# actuator-module.net
KiCad netlist of a schematic drawn in EAGLE
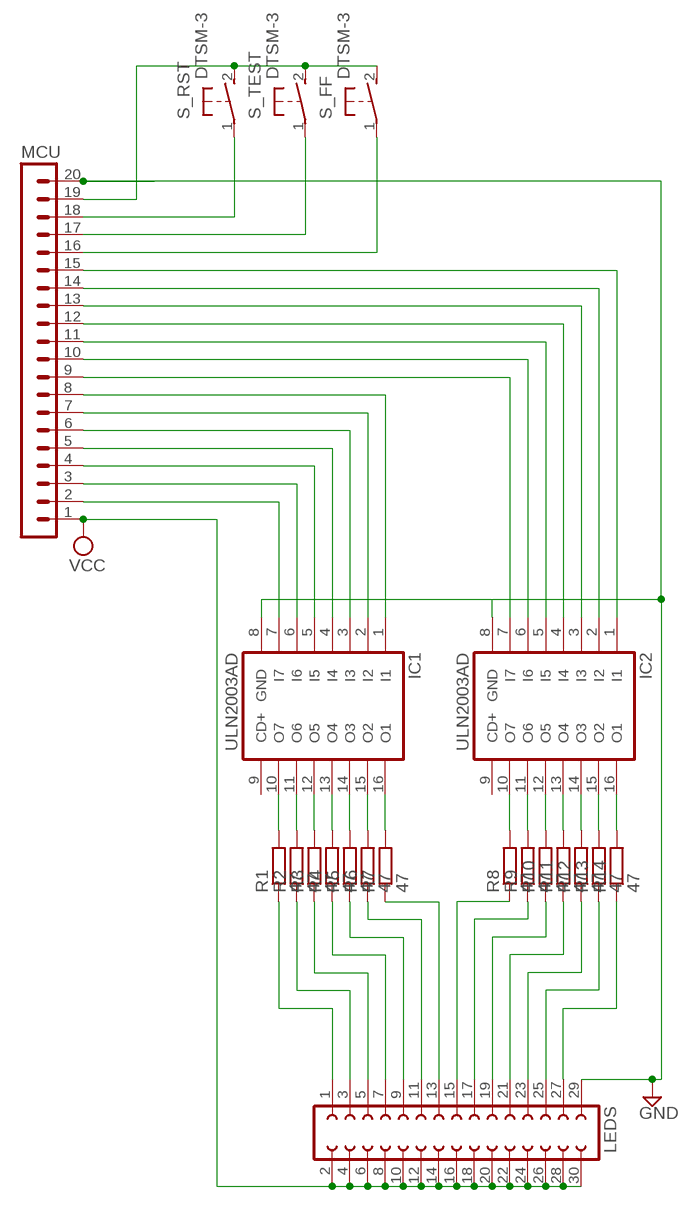
[diagram p0: schematic, sheet 1]

(export (version "E")
  (design (tool "Eeschema 10.0.6"))
  (components
    (comp (ref "IC1")
      (value "ULN2003AD")
      (footprint "eagle-import:SO16")
      (libsource (lib "eagle-import") (part "ULN2003AD"))
    )
    (comp (ref "IC2")
      (value "ULN2003AD")
      (footprint "eagle-import:SO16")
      (libsource (lib "eagle-import") (part "ULN2003AD"))
    )
    (comp (ref "LEDS")
      (value "FE15-2")
      (footprint "eagle-import:FE15-2")
      (libsource (lib "eagle-import") (part "FE15-2"))
    )
    (comp (ref "MCU")
      (value "MA20-1")
      (footprint "eagle-import:MA20-1")
      (libsource (lib "eagle-import") (part "MA20-1"))
    )
    (comp (ref "R1")
      (value "47")
      (footprint "eagle-import:M0805")
      (libsource (lib "eagle-import") (part "R-EU_M0805"))
    )
    (comp (ref "R2")
      (value "47")
      (footprint "eagle-import:M0805")
      (libsource (lib "eagle-import") (part "R-EU_M0805"))
    )
    (comp (ref "R3")
      (value "47")
      (footprint "eagle-import:M0805")
      (libsource (lib "eagle-import") (part "R-EU_M0805"))
    )
    (comp (ref "R4")
      (value "47")
      (footprint "eagle-import:M0805")
      (libsource (lib "eagle-import") (part "R-EU_M0805"))
    )
    (comp (ref "R5")
      (value "47")
      (footprint "eagle-import:M0805")
      (libsource (lib "eagle-import") (part "R-EU_M0805"))
    )
    (comp (ref "R6")
      (value "47")
      (footprint "eagle-import:M0805")
      (libsource (lib "eagle-import") (part "R-EU_M0805"))
    )
    (comp (ref "R7")
      (value "47")
      (footprint "eagle-import:M0805")
      (libsource (lib "eagle-import") (part "R-EU_M0805"))
    )
    (comp (ref "R8")
      (value "47")
      (footprint "eagle-import:M0805")
      (libsource (lib "eagle-import") (part "R-EU_M0805"))
    )
    (comp (ref "R9")
      (value "47")
      (footprint "eagle-import:M0805")
      (libsource (lib "eagle-import") (part "R-EU_M0805"))
    )
    (comp (ref "R10")
      (value "47")
      (footprint "eagle-import:M0805")
      (libsource (lib "eagle-import") (part "R-EU_M0805"))
    )
    (comp (ref "R11")
      (value "47")
      (footprint "eagle-import:M0805")
      (libsource (lib "eagle-import") (part "R-EU_M0805"))
    )
    (comp (ref "R12")
      (value "47")
      (footprint "eagle-import:M0805")
      (libsource (lib "eagle-import") (part "R-EU_M0805"))
    )
    (comp (ref "R13")
      (value "47")
      (footprint "eagle-import:M0805")
      (libsource (lib "eagle-import") (part "R-EU_M0805"))
    )
    (comp (ref "R14")
      (value "47")
      (footprint "eagle-import:M0805")
      (libsource (lib "eagle-import") (part "R-EU_M0805"))
    )
    (comp (ref "S_FF")
      (value "DTSM-3")
      (footprint "eagle-import:DTSM-3")
      (libsource (lib "eagle-import") (part "DTSM-3"))
    )
    (comp (ref "S_RST")
      (value "DTSM-3")
      (footprint "eagle-import:DTSM-3")
      (libsource (lib "eagle-import") (part "DTSM-3"))
    )
    (comp (ref "S_TEST")
      (value "DTSM-3")
      (footprint "eagle-import:DTSM-3")
      (libsource (lib "eagle-import") (part "DTSM-3"))
    )
  )
  (nets
    (net (code "1") (name "GND") (class "Default")
      (node (ref "IC1") (pin "8") (pinfunction "GND_8") (pintype "power_in"))
      (node (ref "IC2") (pin "8") (pinfunction "GND_8") (pintype "power_in"))
      (node (ref "LEDS") (pin "29") (pinfunction "29_29") (pintype "passive"))
      (node (ref "MCU") (pin "20") (pinfunction "20_20") (pintype "passive"))
    )
    (net (code "2") (name "Net-(IC1-I1)") (class "Default")
      (node (ref "IC1") (pin "1") (pinfunction "I1_1") (pintype "input"))
      (node (ref "MCU") (pin "8") (pinfunction "8_8") (pintype "passive"))
    )
    (net (code "3") (name "Net-(IC1-I2)") (class "Default")
      (node (ref "IC1") (pin "2") (pinfunction "I2_2") (pintype "input"))
      (node (ref "MCU") (pin "7") (pinfunction "7_7") (pintype "passive"))
    )
    (net (code "4") (name "Net-(IC1-I3)") (class "Default")
      (node (ref "IC1") (pin "3") (pinfunction "I3_3") (pintype "input"))
      (node (ref "MCU") (pin "6") (pinfunction "6_6") (pintype "passive"))
    )
    (net (code "5") (name "Net-(IC1-I4)") (class "Default")
      (node (ref "IC1") (pin "4") (pinfunction "I4_4") (pintype "input"))
      (node (ref "MCU") (pin "5") (pinfunction "5_5") (pintype "passive"))
    )
    (net (code "6") (name "Net-(IC1-I5)") (class "Default")
      (node (ref "IC1") (pin "5") (pinfunction "I5_5") (pintype "input"))
      (node (ref "MCU") (pin "4") (pinfunction "4_4") (pintype "passive"))
    )
    (net (code "7") (name "Net-(IC1-I6)") (class "Default")
      (node (ref "IC1") (pin "6") (pinfunction "I6_6") (pintype "input"))
      (node (ref "MCU") (pin "3") (pinfunction "3_3") (pintype "passive"))
    )
    (net (code "8") (name "Net-(IC1-I7)") (class "Default")
      (node (ref "IC1") (pin "7") (pinfunction "I7_7") (pintype "input"))
      (node (ref "MCU") (pin "2") (pinfunction "2_2") (pintype "passive"))
    )
    (net (code "9") (name "Net-(IC1-O1)") (class "Default")
      (node (ref "IC1") (pin "16") (pinfunction "O1_16") (pintype "open_collector"))
      (node (ref "R7") (pin "2") (pinfunction "2_2") (pintype "passive"))
    )
    (net (code "10") (name "Net-(IC1-O2)") (class "Default")
      (node (ref "IC1") (pin "15") (pinfunction "O2_15") (pintype "open_collector"))
      (node (ref "R6") (pin "2") (pinfunction "2_2") (pintype "passive"))
    )
    (net (code "11") (name "Net-(IC1-O3)") (class "Default")
      (node (ref "IC1") (pin "14") (pinfunction "O3_14") (pintype "open_collector"))
      (node (ref "R5") (pin "2") (pinfunction "2_2") (pintype "passive"))
    )
    (net (code "12") (name "Net-(IC1-O4)") (class "Default")
      (node (ref "IC1") (pin "13") (pinfunction "O4_13") (pintype "open_collector"))
      (node (ref "R4") (pin "2") (pinfunction "2_2") (pintype "passive"))
    )
    (net (code "13") (name "Net-(IC1-O5)") (class "Default")
      (node (ref "IC1") (pin "12") (pinfunction "O5_12") (pintype "open_collector"))
      (node (ref "R3") (pin "2") (pinfunction "2_2") (pintype "passive"))
    )
    (net (code "14") (name "Net-(IC1-O6)") (class "Default")
      (node (ref "IC1") (pin "11") (pinfunction "O6_11") (pintype "open_collector"))
      (node (ref "R2") (pin "2") (pinfunction "2_2") (pintype "passive"))
    )
    (net (code "15") (name "Net-(IC1-O7)") (class "Default")
      (node (ref "IC1") (pin "10") (pinfunction "O7_10") (pintype "open_collector"))
      (node (ref "R1") (pin "2") (pinfunction "2_2") (pintype "passive"))
    )
    (net (code "16") (name "Net-(IC2-I1)") (class "Default")
      (node (ref "IC2") (pin "1") (pinfunction "I1_1") (pintype "input"))
      (node (ref "MCU") (pin "15") (pinfunction "15_15") (pintype "passive"))
    )
    (net (code "17") (name "Net-(IC2-I2)") (class "Default")
      (node (ref "IC2") (pin "2") (pinfunction "I2_2") (pintype "input"))
      (node (ref "MCU") (pin "14") (pinfunction "14_14") (pintype "passive"))
    )
    (net (code "18") (name "Net-(IC2-I3)") (class "Default")
      (node (ref "IC2") (pin "3") (pinfunction "I3_3") (pintype "input"))
      (node (ref "MCU") (pin "13") (pinfunction "13_13") (pintype "passive"))
    )
    (net (code "19") (name "Net-(IC2-I4)") (class "Default")
      (node (ref "IC2") (pin "4") (pinfunction "I4_4") (pintype "input"))
      (node (ref "MCU") (pin "12") (pinfunction "12_12") (pintype "passive"))
    )
    (net (code "20") (name "Net-(IC2-I5)") (class "Default")
      (node (ref "IC2") (pin "5") (pinfunction "I5_5") (pintype "input"))
      (node (ref "MCU") (pin "11") (pinfunction "11_11") (pintype "passive"))
    )
    (net (code "21") (name "Net-(IC2-I6)") (class "Default")
      (node (ref "IC2") (pin "6") (pinfunction "I6_6") (pintype "input"))
      (node (ref "MCU") (pin "10") (pinfunction "10_10") (pintype "passive"))
    )
    (net (code "22") (name "Net-(IC2-I7)") (class "Default")
      (node (ref "IC2") (pin "7") (pinfunction "I7_7") (pintype "input"))
      (node (ref "MCU") (pin "9") (pinfunction "9_9") (pintype "passive"))
    )
    (net (code "23") (name "Net-(IC2-O1)") (class "Default")
      (node (ref "IC2") (pin "16") (pinfunction "O1_16") (pintype "open_collector"))
      (node (ref "R14") (pin "2") (pinfunction "2_2") (pintype "passive"))
    )
    (net (code "24") (name "Net-(IC2-O2)") (class "Default")
      (node (ref "IC2") (pin "15") (pinfunction "O2_15") (pintype "open_collector"))
      (node (ref "R13") (pin "2") (pinfunction "2_2") (pintype "passive"))
    )
    (net (code "25") (name "Net-(IC2-O3)") (class "Default")
      (node (ref "IC2") (pin "14") (pinfunction "O3_14") (pintype "open_collector"))
      (node (ref "R12") (pin "2") (pinfunction "2_2") (pintype "passive"))
    )
    (net (code "26") (name "Net-(IC2-O4)") (class "Default")
      (node (ref "IC2") (pin "13") (pinfunction "O4_13") (pintype "open_collector"))
      (node (ref "R11") (pin "2") (pinfunction "2_2") (pintype "passive"))
    )
    (net (code "27") (name "Net-(IC2-O5)") (class "Default")
      (node (ref "IC2") (pin "12") (pinfunction "O5_12") (pintype "open_collector"))
      (node (ref "R10") (pin "2") (pinfunction "2_2") (pintype "passive"))
    )
    (net (code "28") (name "Net-(IC2-O6)") (class "Default")
      (node (ref "IC2") (pin "11") (pinfunction "O6_11") (pintype "open_collector"))
      (node (ref "R9") (pin "2") (pinfunction "2_2") (pintype "passive"))
    )
    (net (code "29") (name "Net-(IC2-O7)") (class "Default")
      (node (ref "IC2") (pin "10") (pinfunction "O7_10") (pintype "open_collector"))
      (node (ref "R8") (pin "2") (pinfunction "2_2") (pintype "passive"))
    )
    (net (code "30") (name "Net-(LEDS-Pad1)") (class "Default")
      (node (ref "LEDS") (pin "1") (pinfunction "1_1") (pintype "passive"))
      (node (ref "R1") (pin "1") (pinfunction "1_1") (pintype "passive"))
    )
    (net (code "31") (name "Net-(LEDS-Pad3)") (class "Default")
      (node (ref "LEDS") (pin "3") (pinfunction "3_3") (pintype "passive"))
      (node (ref "R2") (pin "1") (pinfunction "1_1") (pintype "passive"))
    )
    (net (code "32") (name "Net-(LEDS-Pad5)") (class "Default")
      (node (ref "LEDS") (pin "5") (pinfunction "5_5") (pintype "passive"))
      (node (ref "R3") (pin "1") (pinfunction "1_1") (pintype "passive"))
    )
    (net (code "33") (name "Net-(LEDS-Pad7)") (class "Default")
      (node (ref "LEDS") (pin "7") (pinfunction "7_7") (pintype "passive"))
      (node (ref "R4") (pin "1") (pinfunction "1_1") (pintype "passive"))
    )
    (net (code "34") (name "Net-(LEDS-Pad9)") (class "Default")
      (node (ref "LEDS") (pin "9") (pinfunction "9_9") (pintype "passive"))
      (node (ref "R5") (pin "1") (pinfunction "1_1") (pintype "passive"))
    )
    (net (code "35") (name "Net-(LEDS-Pad11)") (class "Default")
      (node (ref "LEDS") (pin "11") (pinfunction "11_11") (pintype "passive"))
      (node (ref "R6") (pin "1") (pinfunction "1_1") (pintype "passive"))
    )
    (net (code "36") (name "Net-(LEDS-Pad13)") (class "Default")
      (node (ref "LEDS") (pin "13") (pinfunction "13_13") (pintype "passive"))
      (node (ref "R7") (pin "1") (pinfunction "1_1") (pintype "passive"))
    )
    (net (code "37") (name "Net-(LEDS-Pad15)") (class "Default")
      (node (ref "LEDS") (pin "15") (pinfunction "15_15") (pintype "passive"))
      (node (ref "R8") (pin "1") (pinfunction "1_1") (pintype "passive"))
    )
    (net (code "38") (name "Net-(LEDS-Pad17)") (class "Default")
      (node (ref "LEDS") (pin "17") (pinfunction "17_17") (pintype "passive"))
      (node (ref "R9") (pin "1") (pinfunction "1_1") (pintype "passive"))
    )
    (net (code "39") (name "Net-(LEDS-Pad19)") (class "Default")
      (node (ref "LEDS") (pin "19") (pinfunction "19_19") (pintype "passive"))
      (node (ref "R10") (pin "1") (pinfunction "1_1") (pintype "passive"))
    )
    (net (code "40") (name "Net-(LEDS-Pad21)") (class "Default")
      (node (ref "LEDS") (pin "21") (pinfunction "21_21") (pintype "passive"))
      (node (ref "R11") (pin "1") (pinfunction "1_1") (pintype "passive"))
    )
    (net (code "41") (name "Net-(LEDS-Pad23)") (class "Default")
      (node (ref "LEDS") (pin "23") (pinfunction "23_23") (pintype "passive"))
      (node (ref "R12") (pin "1") (pinfunction "1_1") (pintype "passive"))
    )
    (net (code "42") (name "Net-(LEDS-Pad25)") (class "Default")
      (node (ref "LEDS") (pin "25") (pinfunction "25_25") (pintype "passive"))
      (node (ref "R13") (pin "1") (pinfunction "1_1") (pintype "passive"))
    )
    (net (code "43") (name "Net-(LEDS-Pad27)") (class "Default")
      (node (ref "LEDS") (pin "27") (pinfunction "27_27") (pintype "passive"))
      (node (ref "R14") (pin "1") (pinfunction "1_1") (pintype "passive"))
    )
    (net (code "44") (name "Net-(MCU-Pad16)") (class "Default")
      (node (ref "MCU") (pin "16") (pinfunction "16_16") (pintype "passive"))
      (node (ref "S_FF") (pin "1") (pinfunction "1_1") (pintype "passive"))
    )
    (net (code "45") (name "Net-(MCU-Pad17)") (class "Default")
      (node (ref "MCU") (pin "17") (pinfunction "17_17") (pintype "passive"))
      (node (ref "S_TEST") (pin "1") (pinfunction "1_1") (pintype "passive"))
    )
    (net (code "46") (name "Net-(MCU-Pad18)") (class "Default")
      (node (ref "MCU") (pin "18") (pinfunction "18_18") (pintype "passive"))
      (node (ref "S_RST") (pin "1") (pinfunction "1_1") (pintype "passive"))
    )
    (net (code "47") (name "Net-(MCU-Pad19)") (class "Default")
      (node (ref "MCU") (pin "19") (pinfunction "19_19") (pintype "passive"))
      (node (ref "S_FF") (pin "2") (pinfunction "2_2") (pintype "passive"))
      (node (ref "S_RST") (pin "2") (pinfunction "2_2") (pintype "passive"))
      (node (ref "S_TEST") (pin "2") (pinfunction "2_2") (pintype "passive"))
    )
    (net (code "48") (name "VCC") (class "Default")
      (node (ref "LEDS") (pin "10") (pinfunction "10_10") (pintype "passive"))
      (node (ref "LEDS") (pin "12") (pinfunction "12_12") (pintype "passive"))
      (node (ref "LEDS") (pin "14") (pinfunction "14_14") (pintype "passive"))
      (node (ref "LEDS") (pin "16") (pinfunction "16_16") (pintype "passive"))
      (node (ref "LEDS") (pin "18") (pinfunction "18_18") (pintype "passive"))
      (node (ref "LEDS") (pin "2") (pinfunction "2_2") (pintype "passive"))
      (node (ref "LEDS") (pin "20") (pinfunction "20_20") (pintype "passive"))
      (node (ref "LEDS") (pin "22") (pinfunction "22_22") (pintype "passive"))
      (node (ref "LEDS") (pin "24") (pinfunction "24_24") (pintype "passive"))
      (node (ref "LEDS") (pin "26") (pinfunction "26_26") (pintype "passive"))
      (node (ref "LEDS") (pin "28") (pinfunction "28_28") (pintype "passive"))
      (node (ref "LEDS") (pin "30") (pinfunction "30_30") (pintype "passive"))
      (node (ref "LEDS") (pin "4") (pinfunction "4_4") (pintype "passive"))
      (node (ref "LEDS") (pin "6") (pinfunction "6_6") (pintype "passive"))
      (node (ref "LEDS") (pin "8") (pinfunction "8_8") (pintype "passive"))
      (node (ref "MCU") (pin "1") (pinfunction "1_1") (pintype "passive"))
    )
    (net (code "49") (name "unconnected-(IC1-CD+-Pad9)") (class "Default")
      (node (ref "IC1") (pin "9") (pinfunction "CD+_9") (pintype "passive"))
    )
    (net (code "50") (name "unconnected-(IC2-CD+-Pad9)") (class "Default")
      (node (ref "IC2") (pin "9") (pinfunction "CD+_9") (pintype "passive"))
    )
  )
)
